# CHIRIMENBasicShield.net
KiCad netlist of a schematic drawn in EAGLE
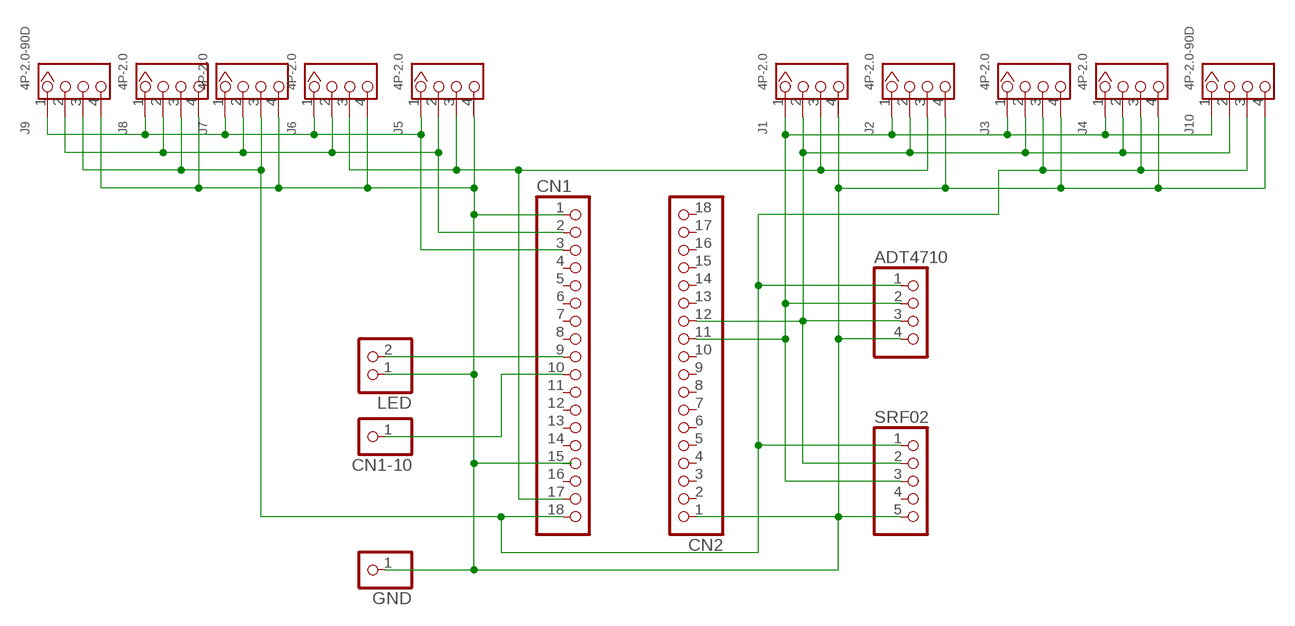
[diagram p0: schematic, sheet 1]

(export (version "E")
  (design (tool "Eeschema 10.0.6"))
  (components
    (comp (ref "ADT4710")
      (value "PINHD-1X4")
      (footprint "eagle-import:1X04")
      (libsource (lib "eagle-import") (part "PINHD-1X4"))
    )
    (comp (ref "CN1")
      (value "PINHD-1X18")
      (footprint "eagle-import:1X18")
      (libsource (lib "eagle-import") (part "PINHD-1X18"))
    )
    (comp (ref "CN1-10")
      (value "PINHD-1X1")
      (footprint "eagle-import:1X01")
      (libsource (lib "eagle-import") (part "PINHD-1X1"))
    )
    (comp (ref "CN2")
      (value "PINHD-1X18")
      (footprint "eagle-import:1X18")
      (libsource (lib "eagle-import") (part "PINHD-1X18"))
    )
    (comp (ref "GND")
      (value "PINHD-1X1")
      (footprint "eagle-import:1X01")
      (libsource (lib "eagle-import") (part "PINHD-1X1"))
    )
    (comp (ref "J1")
      (value "4P-2.0")
      (footprint "eagle-import:HW4-2.0")
      (libsource (lib "eagle-import") (part "GROVE-CONNECTOR-DIP(4P-2.0)"))
    )
    (comp (ref "J2")
      (value "4P-2.0")
      (footprint "eagle-import:HW4-2.0")
      (libsource (lib "eagle-import") (part "GROVE-CONNECTOR-DIP(4P-2.0)"))
    )
    (comp (ref "J3")
      (value "4P-2.0")
      (footprint "eagle-import:HW4-2.0")
      (libsource (lib "eagle-import") (part "GROVE-CONNECTOR-DIP(4P-2.0)"))
    )
    (comp (ref "J4")
      (value "4P-2.0")
      (footprint "eagle-import:HW4-2.0")
      (libsource (lib "eagle-import") (part "GROVE-CONNECTOR-DIP(4P-2.0)"))
    )
    (comp (ref "J5")
      (value "4P-2.0")
      (footprint "eagle-import:HW4-2.0")
      (libsource (lib "eagle-import") (part "GROVE-CONNECTOR-DIP(4P-2.0)"))
    )
    (comp (ref "J6")
      (value "4P-2.0")
      (footprint "eagle-import:HW4-2.0")
      (libsource (lib "eagle-import") (part "GROVE-CONNECTOR-DIP(4P-2.0)"))
    )
    (comp (ref "J7")
      (value "4P-2.0")
      (footprint "eagle-import:HW4-2.0")
      (libsource (lib "eagle-import") (part "GROVE-CONNECTOR-DIP(4P-2.0)"))
    )
    (comp (ref "J8")
      (value "4P-2.0")
      (footprint "eagle-import:HW4-2.0")
      (libsource (lib "eagle-import") (part "GROVE-CONNECTOR-DIP(4P-2.0)"))
    )
    (comp (ref "J9")
      (value "4P-2.0-90D")
      (footprint "eagle-import:HW4-2.0-90D")
      (libsource (lib "eagle-import") (part "GROVE-CONNECTOR-DIP-90D(4P-2.0)"))
    )
    (comp (ref "J10")
      (value "4P-2.0-90D")
      (footprint "eagle-import:HW4-2.0-90D")
      (libsource (lib "eagle-import") (part "GROVE-CONNECTOR-DIP-90D(4P-2.0)"))
    )
    (comp (ref "LED")
      (value "PINHD-1X2")
      (footprint "eagle-import:1X02")
      (libsource (lib "eagle-import") (part "PINHD-1X2"))
    )
    (comp (ref "SRF02")
      (value "PINHD-1X5")
      (footprint "eagle-import:1X05")
      (libsource (lib "eagle-import") (part "PINHD-1X5"))
    )
  )
  (nets
    (net (code "1") (name "Net-(ADT4710-Pad1)") (class "Default")
      (node (ref "ADT4710") (pin "1") (pinfunction "1_1") (pintype "passive"))
      (node (ref "CN1") (pin "18") (pinfunction "18_18") (pintype "passive"))
      (node (ref "J10") (pin "3") (pinfunction "3_3") (pintype "bidirectional"))
      (node (ref "J3") (pin "3") (pinfunction "3_3") (pintype "bidirectional"))
      (node (ref "J4") (pin "3") (pinfunction "3_3") (pintype "bidirectional"))
      (node (ref "J7") (pin "3") (pinfunction "3_3") (pintype "bidirectional"))
      (node (ref "J8") (pin "3") (pinfunction "3_3") (pintype "bidirectional"))
      (node (ref "J9") (pin "3") (pinfunction "3_3") (pintype "bidirectional"))
      (node (ref "SRF02") (pin "1") (pinfunction "1_1") (pintype "passive"))
    )
    (net (code "2") (name "Net-(ADT4710-Pad2)") (class "Default")
      (node (ref "ADT4710") (pin "2") (pinfunction "2_2") (pintype "passive"))
      (node (ref "CN2") (pin "11") (pinfunction "11_11") (pintype "passive"))
      (node (ref "J1") (pin "1") (pinfunction "1_1") (pintype "bidirectional"))
      (node (ref "J10") (pin "1") (pinfunction "1_1") (pintype "bidirectional"))
      (node (ref "J2") (pin "1") (pinfunction "1_1") (pintype "bidirectional"))
      (node (ref "J3") (pin "1") (pinfunction "1_1") (pintype "bidirectional"))
      (node (ref "J4") (pin "1") (pinfunction "1_1") (pintype "bidirectional"))
      (node (ref "SRF02") (pin "3") (pinfunction "3_3") (pintype "passive"))
    )
    (net (code "3") (name "Net-(ADT4710-Pad3)") (class "Default")
      (node (ref "ADT4710") (pin "3") (pinfunction "3_3") (pintype "passive"))
      (node (ref "CN2") (pin "12") (pinfunction "12_12") (pintype "passive"))
      (node (ref "J1") (pin "2") (pinfunction "2_2") (pintype "bidirectional"))
      (node (ref "J10") (pin "2") (pinfunction "2_2") (pintype "bidirectional"))
      (node (ref "J2") (pin "2") (pinfunction "2_2") (pintype "bidirectional"))
      (node (ref "J3") (pin "2") (pinfunction "2_2") (pintype "bidirectional"))
      (node (ref "J4") (pin "2") (pinfunction "2_2") (pintype "bidirectional"))
      (node (ref "SRF02") (pin "2") (pinfunction "2_2") (pintype "passive"))
    )
    (net (code "4") (name "Net-(ADT4710-Pad4)") (class "Default")
      (node (ref "ADT4710") (pin "4") (pinfunction "4_4") (pintype "passive"))
      (node (ref "CN1") (pin "1") (pinfunction "1_1") (pintype "passive"))
      (node (ref "CN2") (pin "1") (pinfunction "1_1") (pintype "passive"))
      (node (ref "GND") (pin "1") (pinfunction "1_1") (pintype "passive"))
      (node (ref "J1") (pin "4") (pinfunction "4_4") (pintype "bidirectional"))
      (node (ref "J10") (pin "4") (pinfunction "4_4") (pintype "bidirectional"))
      (node (ref "J2") (pin "4") (pinfunction "4_4") (pintype "bidirectional"))
      (node (ref "J3") (pin "4") (pinfunction "4_4") (pintype "bidirectional"))
      (node (ref "J4") (pin "4") (pinfunction "4_4") (pintype "bidirectional"))
      (node (ref "J5") (pin "4") (pinfunction "4_4") (pintype "bidirectional"))
      (node (ref "J6") (pin "4") (pinfunction "4_4") (pintype "bidirectional"))
      (node (ref "J7") (pin "4") (pinfunction "4_4") (pintype "bidirectional"))
      (node (ref "J8") (pin "4") (pinfunction "4_4") (pintype "bidirectional"))
      (node (ref "J9") (pin "4") (pinfunction "4_4") (pintype "bidirectional"))
      (node (ref "LED") (pin "1") (pinfunction "1_1") (pintype "passive"))
      (node (ref "SRF02") (pin "5") (pinfunction "5_5") (pintype "passive"))
    )
    (net (code "5") (name "Net-(CN1-10-Pad1)") (class "Default")
      (node (ref "CN1") (pin "10") (pinfunction "10_10") (pintype "passive"))
      (node (ref "CN1-10") (pin "1") (pinfunction "1_1") (pintype "passive"))
    )
    (net (code "6") (name "Net-(CN1-Pad2)") (class "Default")
      (node (ref "CN1") (pin "2") (pinfunction "2_2") (pintype "passive"))
      (node (ref "J5") (pin "2") (pinfunction "2_2") (pintype "bidirectional"))
      (node (ref "J6") (pin "2") (pinfunction "2_2") (pintype "bidirectional"))
      (node (ref "J7") (pin "2") (pinfunction "2_2") (pintype "bidirectional"))
      (node (ref "J8") (pin "2") (pinfunction "2_2") (pintype "bidirectional"))
      (node (ref "J9") (pin "2") (pinfunction "2_2") (pintype "bidirectional"))
    )
    (net (code "7") (name "Net-(CN1-Pad3)") (class "Default")
      (node (ref "CN1") (pin "3") (pinfunction "3_3") (pintype "passive"))
      (node (ref "J5") (pin "1") (pinfunction "1_1") (pintype "bidirectional"))
      (node (ref "J6") (pin "1") (pinfunction "1_1") (pintype "bidirectional"))
      (node (ref "J7") (pin "1") (pinfunction "1_1") (pintype "bidirectional"))
      (node (ref "J8") (pin "1") (pinfunction "1_1") (pintype "bidirectional"))
      (node (ref "J9") (pin "1") (pinfunction "1_1") (pintype "bidirectional"))
    )
    (net (code "8") (name "Net-(CN1-Pad9)") (class "Default")
      (node (ref "CN1") (pin "9") (pinfunction "9_9") (pintype "passive"))
      (node (ref "LED") (pin "2") (pinfunction "2_2") (pintype "passive"))
    )
    (net (code "9") (name "Net-(CN1-Pad17)") (class "Default")
      (node (ref "CN1") (pin "17") (pinfunction "17_17") (pintype "passive"))
      (node (ref "J1") (pin "3") (pinfunction "3_3") (pintype "bidirectional"))
      (node (ref "J2") (pin "3") (pinfunction "3_3") (pintype "bidirectional"))
      (node (ref "J5") (pin "3") (pinfunction "3_3") (pintype "bidirectional"))
      (node (ref "J6") (pin "3") (pinfunction "3_3") (pintype "bidirectional"))
    )
    (net (code "10") (name "unconnected-(CN1-Pad4)") (class "Default")
      (node (ref "CN1") (pin "4") (pinfunction "4_4") (pintype "passive"))
    )
    (net (code "11") (name "unconnected-(CN1-Pad5)") (class "Default")
      (node (ref "CN1") (pin "5") (pinfunction "5_5") (pintype "passive"))
    )
    (net (code "12") (name "unconnected-(CN1-Pad6)") (class "Default")
      (node (ref "CN1") (pin "6") (pinfunction "6_6") (pintype "passive"))
    )
    (net (code "13") (name "unconnected-(CN1-Pad7)") (class "Default")
      (node (ref "CN1") (pin "7") (pinfunction "7_7") (pintype "passive"))
    )
    (net (code "14") (name "unconnected-(CN1-Pad8)") (class "Default")
      (node (ref "CN1") (pin "8") (pinfunction "8_8") (pintype "passive"))
    )
    (net (code "15") (name "unconnected-(CN1-Pad11)") (class "Default")
      (node (ref "CN1") (pin "11") (pinfunction "11_11") (pintype "passive"))
    )
    (net (code "16") (name "unconnected-(CN1-Pad12)") (class "Default")
      (node (ref "CN1") (pin "12") (pinfunction "12_12") (pintype "passive"))
    )
    (net (code "17") (name "unconnected-(CN1-Pad13)") (class "Default")
      (node (ref "CN1") (pin "13") (pinfunction "13_13") (pintype "passive"))
    )
    (net (code "18") (name "unconnected-(CN1-Pad14)") (class "Default")
      (node (ref "CN1") (pin "14") (pinfunction "14_14") (pintype "passive"))
    )
    (net (code "19") (name "unconnected-(CN1-Pad15)") (class "Default")
      (node (ref "CN1") (pin "15") (pinfunction "15_15") (pintype "passive"))
    )
    (net (code "20") (name "unconnected-(CN1-Pad16)") (class "Default")
      (node (ref "CN1") (pin "16") (pinfunction "16_16") (pintype "passive"))
    )
    (net (code "21") (name "unconnected-(CN2-Pad2)") (class "Default")
      (node (ref "CN2") (pin "2") (pinfunction "2_2") (pintype "passive"))
    )
    (net (code "22") (name "unconnected-(CN2-Pad3)") (class "Default")
      (node (ref "CN2") (pin "3") (pinfunction "3_3") (pintype "passive"))
    )
    (net (code "23") (name "unconnected-(CN2-Pad4)") (class "Default")
      (node (ref "CN2") (pin "4") (pinfunction "4_4") (pintype "passive"))
    )
    (net (code "24") (name "unconnected-(CN2-Pad5)") (class "Default")
      (node (ref "CN2") (pin "5") (pinfunction "5_5") (pintype "passive"))
    )
    (net (code "25") (name "unconnected-(CN2-Pad6)") (class "Default")
      (node (ref "CN2") (pin "6") (pinfunction "6_6") (pintype "passive"))
    )
    (net (code "26") (name "unconnected-(CN2-Pad7)") (class "Default")
      (node (ref "CN2") (pin "7") (pinfunction "7_7") (pintype "passive"))
    )
    (net (code "27") (name "unconnected-(CN2-Pad8)") (class "Default")
      (node (ref "CN2") (pin "8") (pinfunction "8_8") (pintype "passive"))
    )
    (net (code "28") (name "unconnected-(CN2-Pad9)") (class "Default")
      (node (ref "CN2") (pin "9") (pinfunction "9_9") (pintype "passive"))
    )
    (net (code "29") (name "unconnected-(CN2-Pad10)") (class "Default")
      (node (ref "CN2") (pin "10") (pinfunction "10_10") (pintype "passive"))
    )
    (net (code "30") (name "unconnected-(CN2-Pad13)") (class "Default")
      (node (ref "CN2") (pin "13") (pinfunction "13_13") (pintype "passive"))
    )
    (net (code "31") (name "unconnected-(CN2-Pad14)") (class "Default")
      (node (ref "CN2") (pin "14") (pinfunction "14_14") (pintype "passive"))
    )
    (net (code "32") (name "unconnected-(CN2-Pad15)") (class "Default")
      (node (ref "CN2") (pin "15") (pinfunction "15_15") (pintype "passive"))
    )
    (net (code "33") (name "unconnected-(CN2-Pad16)") (class "Default")
      (node (ref "CN2") (pin "16") (pinfunction "16_16") (pintype "passive"))
    )
    (net (code "34") (name "unconnected-(CN2-Pad17)") (class "Default")
      (node (ref "CN2") (pin "17") (pinfunction "17_17") (pintype "passive"))
    )
    (net (code "35") (name "unconnected-(CN2-Pad18)") (class "Default")
      (node (ref "CN2") (pin "18") (pinfunction "18_18") (pintype "passive"))
    )
    (net (code "36") (name "unconnected-(SRF02-Pad4)") (class "Default")
      (node (ref "SRF02") (pin "4") (pinfunction "4_4") (pintype "passive"))
    )
  )
)
